# UD3_1_Bootstrap_Gate_Driver.net
KiCad netlist of a schematic drawn in Altium Designer
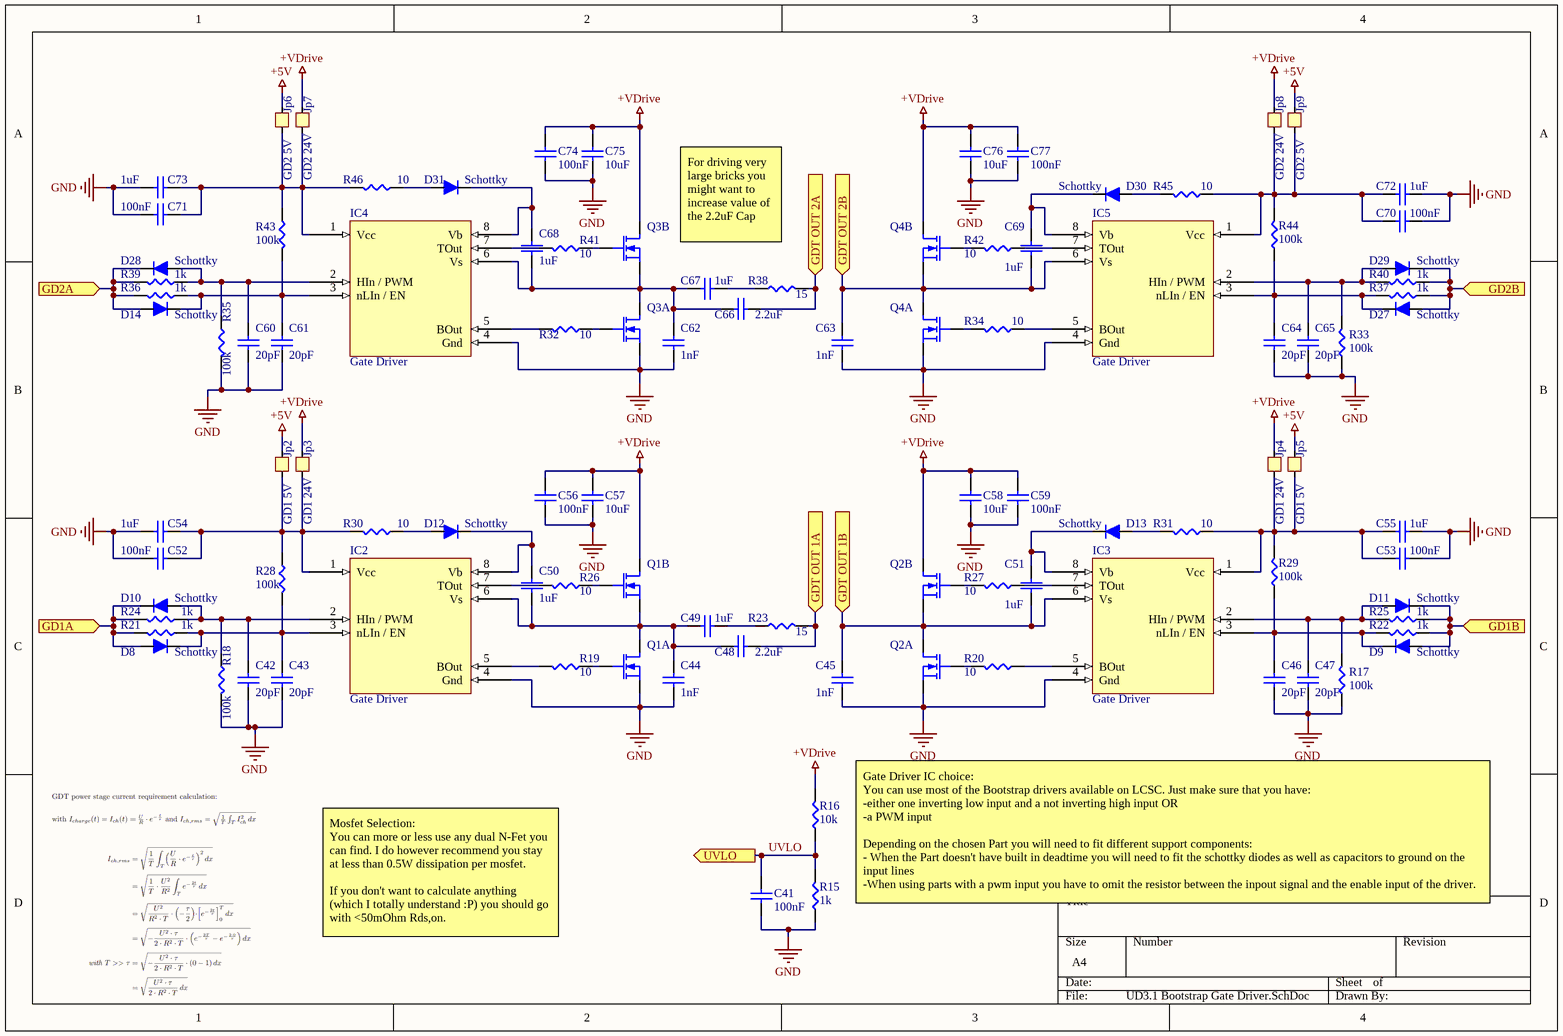
[diagram p0: UD3.1 Bootstrap Gate Driver.SchDoc]

(export (version "E")
  (design (tool "Eeschema 10.0.6"))
  (components
    (comp (ref "C41") (value "100nF") (footprint "0603") (libsource (lib "stdLib") (part "Cap")))
    (comp (ref "C42") (value "20pF") (footprint "0603") (libsource (lib "stdLib") (part "Cap")))
    (comp (ref "C43") (value "20pF") (footprint "0603") (libsource (lib "stdLib") (part "Cap")))
    (comp (ref "C44") (value "1nF") (footprint "0805") (libsource (lib "stdLib") (part "Cap")))
    (comp (ref "C45") (value "1nF") (footprint "0805") (libsource (lib "stdLib") (part "Cap")))
    (comp (ref "C46") (value "20pF") (footprint "0603") (libsource (lib "stdLib") (part "Cap")))
    (comp (ref "C47") (value "20pF") (footprint "0603") (libsource (lib "stdLib") (part "Cap")))
    (comp (ref "C48") (value "2.2uF") (footprint "1206") (libsource (lib "stdLib") (part "Cap")))
    (comp (ref "C49") (value "1uF") (footprint "1206") (libsource (lib "stdLib") (part "Cap")))
    (comp (ref "C50") (value "1uF") (footprint "0805") (libsource (lib "stdLib") (part "Cap")))
    (comp (ref "C51") (value "1uF") (footprint "0805") (libsource (lib "stdLib") (part "Cap")))
    (comp (ref "C52") (value "100nF") (footprint "0603") (libsource (lib "stdLib") (part "Cap")))
    (comp (ref "C53") (value "100nF") (footprint "0603") (libsource (lib "stdLib") (part "Cap")))
    (comp (ref "C54") (value "1uF") (footprint "0805") (libsource (lib "stdLib") (part "Cap")))
    (comp (ref "C55") (value "1uF") (footprint "0805") (libsource (lib "stdLib") (part "Cap")))
    (comp (ref "C56") (value "100nF") (footprint "0603") (libsource (lib "stdLib") (part "Cap")))
    (comp (ref "C57") (value "10uF") (footprint "0805") (libsource (lib "stdLib") (part "Cap")))
    (comp (ref "C58") (value "10uF") (footprint "0805") (libsource (lib "stdLib") (part "Cap")))
    (comp (ref "C59") (value "100nF") (footprint "0603") (libsource (lib "stdLib") (part "Cap")))
    (comp (ref "C60") (value "20pF") (footprint "0603") (libsource (lib "stdLib") (part "Cap")))
    (comp (ref "C61") (value "20pF") (footprint "0603") (libsource (lib "stdLib") (part "Cap")))
    (comp (ref "C62") (value "1nF") (footprint "0805") (libsource (lib "stdLib") (part "Cap")))
    (comp (ref "C63") (value "1nF") (footprint "0805") (libsource (lib "stdLib") (part "Cap")))
    (comp (ref "C64") (value "20pF") (footprint "0603") (libsource (lib "stdLib") (part "Cap")))
    (comp (ref "C65") (value "20pF") (footprint "0603") (libsource (lib "stdLib") (part "Cap")))
    (comp (ref "C66") (value "2.2uF") (footprint "1206") (libsource (lib "stdLib") (part "Cap")))
    (comp (ref "C67") (value "1uF") (footprint "1206") (libsource (lib "stdLib") (part "Cap")))
    (comp (ref "C68") (value "1uF") (footprint "0805") (libsource (lib "stdLib") (part "Cap")))
    (comp (ref "C69") (value "1uF") (footprint "0805") (libsource (lib "stdLib") (part "Cap")))
    (comp (ref "C70") (value "100nF") (footprint "0805") (libsource (lib "stdLib") (part "Cap")))
    (comp (ref "C71") (value "100nF") (footprint "0805") (libsource (lib "stdLib") (part "Cap")))
    (comp (ref "C72") (value "1uF") (footprint "0805") (libsource (lib "stdLib") (part "Cap")))
    (comp (ref "C73") (value "1uF") (footprint "0805") (libsource (lib "stdLib") (part "Cap")))
    (comp (ref "C74") (value "100nF") (footprint "0805") (libsource (lib "stdLib") (part "Cap")))
    (comp (ref "C75") (value "10uF") (footprint "0805") (libsource (lib "stdLib") (part "Cap")))
    (comp (ref "C76") (value "10uF") (footprint "0805") (libsource (lib "stdLib") (part "Cap")))
    (comp (ref "C77") (value "100nF") (footprint "0805") (libsource (lib "stdLib") (part "Cap")))
    (comp (ref "D8")
      (value "Schottky")
      (footprint "SOD523")
      (description "Cmon its a diode what more do I need to say?")
      (libsource (lib "stdLib") (part "Diode"))
    )
    (comp (ref "D9")
      (value "Schottky")
      (footprint "SOD523")
      (description "Cmon its a diode what more do I need to say?")
      (libsource (lib "stdLib") (part "Diode"))
    )
    (comp (ref "D10")
      (value "Schottky")
      (footprint "SOD523")
      (description "Cmon its a diode what more do I need to say?")
      (libsource (lib "stdLib") (part "Diode"))
    )
    (comp (ref "D11")
      (value "Schottky")
      (footprint "SOD523")
      (description "Cmon its a diode what more do I need to say?")
      (libsource (lib "stdLib") (part "Diode"))
    )
    (comp (ref "D12")
      (value "Schottky")
      (footprint "SOD523")
      (description "Cmon its a diode what more do I need to say?")
      (libsource (lib "stdLib") (part "Diode"))
    )
    (comp (ref "D13")
      (value "Schottky")
      (footprint "SOD523")
      (description "Cmon its a diode what more do I need to say?")
      (libsource (lib "stdLib") (part "Diode"))
    )
    (comp (ref "D14")
      (value "Schottky")
      (footprint "SOD523")
      (description "Cmon its a diode what more do I need to say?")
      (libsource (lib "stdLib") (part "Diode"))
    )
    (comp (ref "D27")
      (value "Schottky")
      (footprint "SOD523")
      (description "Cmon its a diode what more do I need to say?")
      (libsource (lib "stdLib") (part "Diode"))
    )
    (comp (ref "D28")
      (value "Schottky")
      (footprint "SOD523")
      (description "Cmon its a diode what more do I need to say?")
      (libsource (lib "stdLib") (part "Diode"))
    )
    (comp (ref "D29")
      (value "Schottky")
      (footprint "SOD523")
      (description "Cmon its a diode what more do I need to say?")
      (libsource (lib "stdLib") (part "Diode"))
    )
    (comp (ref "D30")
      (value "Schottky")
      (footprint "SOD523")
      (description "Cmon its a diode what more do I need to say?")
      (libsource (lib "stdLib") (part "Diode"))
    )
    (comp (ref "D31")
      (value "Schottky")
      (footprint "SOD523")
      (description "Cmon its a diode what more do I need to say?")
      (libsource (lib "stdLib") (part "Diode"))
    )
    (comp (ref "IC2")
      (value "Gate Driver")
      (footprint "SOIC8")
      (description "Bootstrappable half bridge driver IC")
      (libsource (lib "stdLib") (part "Gatedriver Bootstrap"))
    )
    (comp (ref "IC3")
      (value "Gate Driver")
      (footprint "SOIC8")
      (description "Bootstrappable half bridge driver IC")
      (libsource (lib "") (part "Gatedriver Bootstrap_1"))
    )
    (comp (ref "IC4")
      (value "Gate Driver")
      (footprint "SOIC8")
      (description "Bootstrappable half bridge driver IC")
      (libsource (lib "stdLib") (part "Gatedriver Bootstrap"))
    )
    (comp (ref "IC5")
      (value "Gate Driver")
      (footprint "SOIC8")
      (description "Bootstrappable half bridge driver IC")
      (libsource (lib "") (part "Gatedriver Bootstrap_1"))
    )
    (comp (ref "Jp2") (value "GD1 5V") (footprint "PCB Jumper NO") (libsource (lib "") (part "Jumper_1")))
    (comp (ref "Jp3") (value "GD1 24V") (footprint "PCB Jumper NO") (libsource (lib "") (part "Jumper_1")))
    (comp (ref "Jp4")
      (value "GD1 24V")
      (footprint "PCB Jumper NO")
      (libsource (lib "stdLib") (part "Jumper"))
    )
    (comp (ref "Jp5") (value "GD1 5V") (footprint "PCB Jumper NO") (libsource (lib "stdLib") (part "Jumper")))
    (comp (ref "Jp6") (value "GD2 5V") (footprint "PCB Jumper NO") (libsource (lib "") (part "Jumper_1")))
    (comp (ref "Jp7") (value "GD2 24V") (footprint "PCB Jumper NO") (libsource (lib "") (part "Jumper_1")))
    (comp (ref "Jp8")
      (value "GD2 24V")
      (footprint "PCB Jumper NO")
      (libsource (lib "stdLib") (part "Jumper"))
    )
    (comp (ref "Jp9") (value "GD2 5V") (footprint "PCB Jumper NO") (libsource (lib "stdLib") (part "Jumper")))
    (comp (ref "Q1")
      (value "Dual NFet")
      (footprint "SO-8FL - Dual")
      (description "Dual Mosfet, two N channel")
      (libsource (lib "stdLib") (part "Mosfet 2N"))
    )
    (comp (ref "Q2")
      (value "Dual NFet")
      (footprint "SO-8FL - Dual")
      (description "Dual Mosfet, two N channel")
      (libsource (lib "stdLib") (part "Mosfet 2N"))
    )
    (comp (ref "Q3")
      (value "Dual NFet")
      (footprint "SO-8FL - Dual")
      (description "Dual Mosfet, two N channel")
      (libsource (lib "stdLib") (part "Mosfet 2N"))
    )
    (comp (ref "Q4")
      (value "Dual NFet")
      (footprint "SO-8FL - Dual")
      (description "Dual Mosfet, two N channel")
      (libsource (lib "stdLib") (part "Mosfet 2N"))
    )
    (comp (ref "R15") (value "1k") (footprint "0603") (libsource (lib "stdLib") (part "Resistor")))
    (comp (ref "R16") (value "10k") (footprint "0603") (libsource (lib "stdLib") (part "Resistor")))
    (comp (ref "R17") (value "100k") (footprint "0603") (libsource (lib "stdLib") (part "Resistor")))
    (comp (ref "R18") (value "100k") (footprint "0603") (libsource (lib "stdLib") (part "Resistor")))
    (comp (ref "R19") (value "10") (footprint "0805") (libsource (lib "stdLib") (part "Resistor")))
    (comp (ref "R20") (value "10") (footprint "0805") (libsource (lib "stdLib") (part "Resistor")))
    (comp (ref "R21") (value "1k") (footprint "0603") (libsource (lib "stdLib") (part "Resistor")))
    (comp (ref "R22") (value "1k") (footprint "0603") (libsource (lib "stdLib") (part "Resistor")))
    (comp (ref "R23") (value "15") (footprint "1206") (libsource (lib "stdLib") (part "Resistor")))
    (comp (ref "R24") (value "1k") (footprint "0603") (libsource (lib "stdLib") (part "Resistor")))
    (comp (ref "R25") (value "1k") (footprint "0603") (libsource (lib "stdLib") (part "Resistor")))
    (comp (ref "R26") (value "10") (footprint "0805") (libsource (lib "stdLib") (part "Resistor")))
    (comp (ref "R27") (value "10") (footprint "0805") (libsource (lib "stdLib") (part "Resistor")))
    (comp (ref "R28") (value "100k") (footprint "0603") (libsource (lib "stdLib") (part "Resistor")))
    (comp (ref "R29") (value "100k") (footprint "0603") (libsource (lib "stdLib") (part "Resistor")))
    (comp (ref "R30") (value "10") (footprint "0603") (libsource (lib "stdLib") (part "Resistor")))
    (comp (ref "R31") (value "10") (footprint "0603") (libsource (lib "stdLib") (part "Resistor")))
    (comp (ref "R32") (value "10") (footprint "0805") (libsource (lib "stdLib") (part "Resistor")))
    (comp (ref "R33") (value "100k") (footprint "0603") (libsource (lib "stdLib") (part "Resistor")))
    (comp (ref "R34") (value "10") (footprint "0805") (libsource (lib "stdLib") (part "Resistor")))
    (comp (ref "R35") (value "100k") (footprint "0603") (libsource (lib "stdLib") (part "Resistor")))
    (comp (ref "R36") (value "1k") (footprint "0603") (libsource (lib "stdLib") (part "Resistor")))
    (comp (ref "R37") (value "1k") (footprint "0603") (libsource (lib "stdLib") (part "Resistor")))
    (comp (ref "R38") (value "15") (footprint "1206") (libsource (lib "stdLib") (part "Resistor")))
    (comp (ref "R39") (value "1k") (footprint "0603") (libsource (lib "stdLib") (part "Resistor")))
    (comp (ref "R40") (value "1k") (footprint "0603") (libsource (lib "stdLib") (part "Resistor")))
    (comp (ref "R41") (value "10") (footprint "0805") (libsource (lib "stdLib") (part "Resistor")))
    (comp (ref "R42") (value "10") (footprint "0805") (libsource (lib "stdLib") (part "Resistor")))
    (comp (ref "R43") (value "100k") (footprint "0603") (libsource (lib "stdLib") (part "Resistor")))
    (comp (ref "R44") (value "100k") (footprint "0603") (libsource (lib "stdLib") (part "Resistor")))
    (comp (ref "R45") (value "10") (footprint "0603") (libsource (lib "stdLib") (part "Resistor")))
    (comp (ref "R46") (value "10") (footprint "0603") (libsource (lib "stdLib") (part "Resistor")))
  )
  (nets
    (net (code "1") (name "+5V") (class "Default")
      (node (ref "Jp2") (pin "2") (pinfunction "2_2") (pintype "passive"))
      (node (ref "Jp5") (pin "2") (pinfunction "2_2") (pintype "passive"))
      (node (ref "Jp6") (pin "2") (pinfunction "2_2") (pintype "passive"))
      (node (ref "Jp9") (pin "2") (pinfunction "2_2") (pintype "passive"))
    )
    (net (code "2") (name "+VDrive") (class "Default")
      (node (ref "C56") (pin "2") (pinfunction "2_2") (pintype "passive"))
      (node (ref "C57") (pin "2") (pinfunction "2_2") (pintype "passive"))
      (node (ref "C58") (pin "2") (pinfunction "2_2") (pintype "passive"))
      (node (ref "C59") (pin "2") (pinfunction "2_2") (pintype "passive"))
      (node (ref "C74") (pin "2") (pinfunction "2_2") (pintype "passive"))
      (node (ref "C75") (pin "2") (pinfunction "2_2") (pintype "passive"))
      (node (ref "C76") (pin "2") (pinfunction "2_2") (pintype "passive"))
      (node (ref "C77") (pin "2") (pinfunction "2_2") (pintype "passive"))
      (node (ref "Jp3") (pin "2") (pinfunction "2_2") (pintype "passive"))
      (node (ref "Jp4") (pin "2") (pinfunction "2_2") (pintype "passive"))
      (node (ref "Jp7") (pin "2") (pinfunction "2_2") (pintype "passive"))
      (node (ref "Jp8") (pin "2") (pinfunction "2_2") (pintype "passive"))
      (node (ref "Q1") (pin "D1") (pinfunction "D1_D1") (pintype "passive"))
      (node (ref "Q2") (pin "D1") (pinfunction "D1_D1") (pintype "passive"))
      (node (ref "Q3") (pin "D1") (pinfunction "D1_D1") (pintype "passive"))
      (node (ref "Q4") (pin "D1") (pinfunction "D1_D1") (pintype "passive"))
      (node (ref "R16") (pin "1") (pinfunction "1_1") (pintype "passive"))
    )
    (net (code "3") (name "/GD1A") (class "Default")
      (node (ref "D10") (pin "2") (pintype "passive"))
      (node (ref "D8") (pin "1") (pintype "passive"))
      (node (ref "R21") (pin "1") (pinfunction "1_1") (pintype "passive"))
      (node (ref "R24") (pin "1") (pinfunction "1_1") (pintype "passive"))
    )
    (net (code "4") (name "/GD1B") (class "Default")
      (node (ref "D11") (pin "2") (pintype "passive"))
      (node (ref "D9") (pin "1") (pintype "passive"))
      (node (ref "R22") (pin "1") (pinfunction "1_1") (pintype "passive"))
      (node (ref "R25") (pin "1") (pinfunction "1_1") (pintype "passive"))
    )
    (net (code "5") (name "/GD2A") (class "Default")
      (node (ref "D14") (pin "1") (pintype "passive"))
      (node (ref "D28") (pin "2") (pintype "passive"))
      (node (ref "R36") (pin "1") (pinfunction "1_1") (pintype "passive"))
      (node (ref "R39") (pin "1") (pinfunction "1_1") (pintype "passive"))
    )
    (net (code "6") (name "/GD2B") (class "Default")
      (node (ref "D27") (pin "1") (pintype "passive"))
      (node (ref "D29") (pin "2") (pintype "passive"))
      (node (ref "R37") (pin "1") (pinfunction "1_1") (pintype "passive"))
      (node (ref "R40") (pin "1") (pinfunction "1_1") (pintype "passive"))
    )
    (net (code "7") (name "/GDT OUT 1A") (class "Default")
      (node (ref "C48") (pin "2") (pinfunction "2_2") (pintype "passive"))
      (node (ref "R23") (pin "2") (pinfunction "2_2") (pintype "passive"))
    )
    (net (code "8") (name "/GDT OUT 1B") (class "Default")
      (node (ref "C45") (pin "2") (pinfunction "2_2") (pintype "passive"))
      (node (ref "C51") (pin "1") (pinfunction "1_1") (pintype "passive"))
      (node (ref "IC3") (pin "6") (pinfunction "Vs_6") (pintype "input"))
      (node (ref "Q2") (pin "D2") (pinfunction "D2_D2") (pintype "passive"))
      (node (ref "Q2") (pin "S1") (pinfunction "S1_S1") (pintype "passive"))
    )
    (net (code "9") (name "/GDT OUT 2A") (class "Default")
      (node (ref "C66") (pin "2") (pinfunction "2_2") (pintype "passive"))
      (node (ref "R38") (pin "2") (pinfunction "2_2") (pintype "passive"))
    )
    (net (code "10") (name "/GDT OUT 2B") (class "Default")
      (node (ref "C63") (pin "2") (pinfunction "2_2") (pintype "passive"))
      (node (ref "C69") (pin "1") (pinfunction "1_1") (pintype "passive"))
      (node (ref "IC5") (pin "6") (pinfunction "Vs_6") (pintype "input"))
      (node (ref "Q4") (pin "D2") (pinfunction "D2_D2") (pintype "passive"))
      (node (ref "Q4") (pin "S1") (pinfunction "S1_S1") (pintype "passive"))
    )
    (net (code "11") (name "/UVLO") (class "Default")
      (node (ref "C41") (pin "2") (pinfunction "2_2") (pintype "passive"))
      (node (ref "R15") (pin "1") (pinfunction "1_1") (pintype "passive"))
      (node (ref "R16") (pin "2") (pinfunction "2_2") (pintype "passive"))
    )
    (net (code "12") (name "GND") (class "Default")
      (node (ref "C41") (pin "1") (pinfunction "1_1") (pintype "passive"))
      (node (ref "C42") (pin "2") (pinfunction "2_2") (pintype "passive"))
      (node (ref "C43") (pin "2") (pinfunction "2_2") (pintype "passive"))
      (node (ref "C44") (pin "1") (pinfunction "1_1") (pintype "passive"))
      (node (ref "C45") (pin "1") (pinfunction "1_1") (pintype "passive"))
      (node (ref "C46") (pin "2") (pinfunction "2_2") (pintype "passive"))
      (node (ref "C47") (pin "2") (pinfunction "2_2") (pintype "passive"))
      (node (ref "C52") (pin "2") (pinfunction "2_2") (pintype "passive"))
      (node (ref "C53") (pin "2") (pinfunction "2_2") (pintype "passive"))
      (node (ref "C54") (pin "2") (pinfunction "2_2") (pintype "passive"))
      (node (ref "C55") (pin "2") (pinfunction "2_2") (pintype "passive"))
      (node (ref "C56") (pin "1") (pinfunction "1_1") (pintype "passive"))
      (node (ref "C57") (pin "1") (pinfunction "1_1") (pintype "passive"))
      (node (ref "C58") (pin "1") (pinfunction "1_1") (pintype "passive"))
      (node (ref "C59") (pin "1") (pinfunction "1_1") (pintype "passive"))
      (node (ref "C60") (pin "2") (pinfunction "2_2") (pintype "passive"))
      (node (ref "C61") (pin "2") (pinfunction "2_2") (pintype "passive"))
      (node (ref "C62") (pin "1") (pinfunction "1_1") (pintype "passive"))
      (node (ref "C63") (pin "1") (pinfunction "1_1") (pintype "passive"))
      (node (ref "C64") (pin "2") (pinfunction "2_2") (pintype "passive"))
      (node (ref "C65") (pin "2") (pinfunction "2_2") (pintype "passive"))
      (node (ref "C70") (pin "2") (pinfunction "2_2") (pintype "passive"))
      (node (ref "C71") (pin "2") (pinfunction "2_2") (pintype "passive"))
      (node (ref "C72") (pin "2") (pinfunction "2_2") (pintype "passive"))
      (node (ref "C73") (pin "2") (pinfunction "2_2") (pintype "passive"))
      (node (ref "C74") (pin "1") (pinfunction "1_1") (pintype "passive"))
      (node (ref "C75") (pin "1") (pinfunction "1_1") (pintype "passive"))
      (node (ref "C76") (pin "1") (pinfunction "1_1") (pintype "passive"))
      (node (ref "C77") (pin "1") (pinfunction "1_1") (pintype "passive"))
      (node (ref "IC2") (pin "4") (pinfunction "Gnd_4") (pintype "input"))
      (node (ref "IC3") (pin "4") (pinfunction "Gnd_4") (pintype "input"))
      (node (ref "IC4") (pin "4") (pinfunction "Gnd_4") (pintype "input"))
      (node (ref "IC5") (pin "4") (pinfunction "Gnd_4") (pintype "input"))
      (node (ref "Q1") (pin "S2") (pinfunction "S2_S2") (pintype "passive"))
      (node (ref "Q2") (pin "S2") (pinfunction "S2_S2") (pintype "passive"))
      (node (ref "Q3") (pin "S2") (pinfunction "S2_S2") (pintype "passive"))
      (node (ref "Q4") (pin "S2") (pinfunction "S2_S2") (pintype "passive"))
      (node (ref "R15") (pin "2") (pinfunction "2_2") (pintype "passive"))
      (node (ref "R17") (pin "1") (pinfunction "1_1") (pintype "passive"))
      (node (ref "R18") (pin "1") (pinfunction "1_1") (pintype "passive"))
      (node (ref "R33") (pin "1") (pinfunction "1_1") (pintype "passive"))
      (node (ref "R35") (pin "1") (pinfunction "1_1") (pintype "passive"))
    )
    (net (code "13") (name "Net-(C49-Pad2)") (class "Default")
      (node (ref "C49") (pin "2") (pinfunction "2_2") (pintype "passive"))
      (node (ref "R23") (pin "1") (pinfunction "1_1") (pintype "passive"))
    )
    (net (code "14") (name "Net-(C67-Pad2)") (class "Default")
      (node (ref "C67") (pin "2") (pinfunction "2_2") (pintype "passive"))
      (node (ref "R38") (pin "1") (pinfunction "1_1") (pintype "passive"))
    )
    (net (code "15") (name "Net-(D12-Pad1)") (class "Default")
      (node (ref "D12") (pin "1") (pintype "passive"))
      (node (ref "R30") (pin "2") (pinfunction "2_2") (pintype "passive"))
    )
    (net (code "16") (name "Net-(D13-Pad1)") (class "Default")
      (node (ref "D13") (pin "1") (pintype "passive"))
      (node (ref "R31") (pin "2") (pinfunction "2_2") (pintype "passive"))
    )
    (net (code "17") (name "Net-(D30-Pad1)") (class "Default")
      (node (ref "D30") (pin "1") (pintype "passive"))
      (node (ref "R45") (pin "2") (pinfunction "2_2") (pintype "passive"))
    )
    (net (code "18") (name "Net-(D31-Pad1)") (class "Default")
      (node (ref "D31") (pin "1") (pintype "passive"))
      (node (ref "R46") (pin "2") (pinfunction "2_2") (pintype "passive"))
    )
    (net (code "19") (name "Net-(IC2-BOut)") (class "Default")
      (node (ref "IC2") (pin "5") (pinfunction "BOut_5") (pintype "input"))
      (node (ref "R19") (pin "1") (pinfunction "1_1") (pintype "passive"))
    )
    (net (code "20") (name "Net-(IC2-HIn_{slash}_PWM)") (class "Default")
      (node (ref "C42") (pin "1") (pinfunction "1_1") (pintype "passive"))
      (node (ref "D10") (pin "1") (pintype "passive"))
      (node (ref "IC2") (pin "2") (pinfunction "HIn_/_PWM_2") (pintype "input"))
      (node (ref "R18") (pin "2") (pinfunction "2_2") (pintype "passive"))
      (node (ref "R24") (pin "2") (pinfunction "2_2") (pintype "passive"))
    )
    (net (code "21") (name "Net-(IC2-TOut)") (class "Default")
      (node (ref "IC2") (pin "7") (pinfunction "TOut_7") (pintype "input"))
      (node (ref "R26") (pin "1") (pinfunction "1_1") (pintype "passive"))
    )
    (net (code "22") (name "Net-(IC2-Vb)") (class "Default")
      (node (ref "C50") (pin "2") (pinfunction "2_2") (pintype "passive"))
      (node (ref "D12") (pin "2") (pintype "passive"))
      (node (ref "IC2") (pin "8") (pinfunction "Vb_8") (pintype "input"))
    )
    (net (code "23") (name "Net-(IC2-Vcc)") (class "Default")
      (node (ref "C52") (pin "1") (pinfunction "1_1") (pintype "passive"))
      (node (ref "C54") (pin "1") (pinfunction "1_1") (pintype "passive"))
      (node (ref "IC2") (pin "1") (pinfunction "Vcc_1") (pintype "input"))
      (node (ref "Jp2") (pin "1") (pinfunction "1_1") (pintype "passive"))
      (node (ref "Jp3") (pin "1") (pinfunction "1_1") (pintype "passive"))
      (node (ref "R28") (pin "2") (pinfunction "2_2") (pintype "passive"))
      (node (ref "R30") (pin "1") (pinfunction "1_1") (pintype "passive"))
    )
    (net (code "24") (name "Net-(IC2-Vs)") (class "Default")
      (node (ref "C44") (pin "2") (pinfunction "2_2") (pintype "passive"))
      (node (ref "C48") (pin "1") (pinfunction "1_1") (pintype "passive"))
      (node (ref "C49") (pin "1") (pinfunction "1_1") (pintype "passive"))
      (node (ref "C50") (pin "1") (pinfunction "1_1") (pintype "passive"))
      (node (ref "IC2") (pin "6") (pinfunction "Vs_6") (pintype "input"))
      (node (ref "Q1") (pin "D2") (pinfunction "D2_D2") (pintype "passive"))
      (node (ref "Q1") (pin "S1") (pinfunction "S1_S1") (pintype "passive"))
    )
    (net (code "25") (name "Net-(IC2-nLIn_{slash}_EN)") (class "Default")
      (node (ref "C43") (pin "1") (pinfunction "1_1") (pintype "passive"))
      (node (ref "D8") (pin "2") (pintype "passive"))
      (node (ref "IC2") (pin "3") (pinfunction "nLIn_/_EN_3") (pintype "input"))
      (node (ref "R21") (pin "2") (pinfunction "2_2") (pintype "passive"))
      (node (ref "R28") (pin "1") (pinfunction "1_1") (pintype "passive"))
    )
    (net (code "26") (name "Net-(IC3-BOut)") (class "Default")
      (node (ref "IC3") (pin "5") (pinfunction "BOut_5") (pintype "input"))
      (node (ref "R20") (pin "1") (pinfunction "1_1") (pintype "passive"))
    )
    (net (code "27") (name "Net-(IC3-HIn_{slash}_PWM)") (class "Default")
      (node (ref "C47") (pin "1") (pinfunction "1_1") (pintype "passive"))
      (node (ref "D11") (pin "1") (pintype "passive"))
      (node (ref "IC3") (pin "2") (pinfunction "HIn_/_PWM_2") (pintype "input"))
      (node (ref "R17") (pin "2") (pinfunction "2_2") (pintype "passive"))
      (node (ref "R25") (pin "2") (pinfunction "2_2") (pintype "passive"))
    )
    (net (code "28") (name "Net-(IC3-TOut)") (class "Default")
      (node (ref "IC3") (pin "7") (pinfunction "TOut_7") (pintype "input"))
      (node (ref "R27") (pin "1") (pinfunction "1_1") (pintype "passive"))
    )
    (net (code "29") (name "Net-(IC3-Vb)") (class "Default")
      (node (ref "C51") (pin "2") (pinfunction "2_2") (pintype "passive"))
      (node (ref "D13") (pin "2") (pintype "passive"))
      (node (ref "IC3") (pin "8") (pinfunction "Vb_8") (pintype "input"))
    )
    (net (code "30") (name "Net-(IC3-Vcc)") (class "Default")
      (node (ref "C53") (pin "1") (pinfunction "1_1") (pintype "passive"))
      (node (ref "C55") (pin "1") (pinfunction "1_1") (pintype "passive"))
      (node (ref "IC3") (pin "1") (pinfunction "Vcc_1") (pintype "input"))
      (node (ref "Jp4") (pin "1") (pinfunction "1_1") (pintype "passive"))
      (node (ref "Jp5") (pin "1") (pinfunction "1_1") (pintype "passive"))
      (node (ref "R29") (pin "2") (pinfunction "2_2") (pintype "passive"))
      (node (ref "R31") (pin "1") (pinfunction "1_1") (pintype "passive"))
    )
    (net (code "31") (name "Net-(IC3-nLIn_{slash}_EN)") (class "Default")
      (node (ref "C46") (pin "1") (pinfunction "1_1") (pintype "passive"))
      (node (ref "D9") (pin "2") (pintype "passive"))
      (node (ref "IC3") (pin "3") (pinfunction "nLIn_/_EN_3") (pintype "input"))
      (node (ref "R22") (pin "2") (pinfunction "2_2") (pintype "passive"))
      (node (ref "R29") (pin "1") (pinfunction "1_1") (pintype "passive"))
    )
    (net (code "32") (name "Net-(IC4-BOut)") (class "Default")
      (node (ref "IC4") (pin "5") (pinfunction "BOut_5") (pintype "input"))
      (node (ref "R32") (pin "1") (pinfunction "1_1") (pintype "passive"))
    )
    (net (code "33") (name "Net-(IC4-HIn_{slash}_PWM)") (class "Default")
      (node (ref "C60") (pin "1") (pinfunction "1_1") (pintype "passive"))
      (node (ref "D28") (pin "1") (pintype "passive"))
      (node (ref "IC4") (pin "2") (pinfunction "HIn_/_PWM_2") (pintype "input"))
      (node (ref "R35") (pin "2") (pinfunction "2_2") (pintype "passive"))
      (node (ref "R39") (pin "2") (pinfunction "2_2") (pintype "passive"))
    )
    (net (code "34") (name "Net-(IC4-TOut)") (class "Default")
      (node (ref "IC4") (pin "7") (pinfunction "TOut_7") (pintype "input"))
      (node (ref "R41") (pin "1") (pinfunction "1_1") (pintype "passive"))
    )
    (net (code "35") (name "Net-(IC4-Vb)") (class "Default")
      (node (ref "C68") (pin "2") (pinfunction "2_2") (pintype "passive"))
      (node (ref "D31") (pin "2") (pintype "passive"))
      (node (ref "IC4") (pin "8") (pinfunction "Vb_8") (pintype "input"))
    )
    (net (code "36") (name "Net-(IC4-Vcc)") (class "Default")
      (node (ref "C71") (pin "1") (pinfunction "1_1") (pintype "passive"))
      (node (ref "C73") (pin "1") (pinfunction "1_1") (pintype "passive"))
      (node (ref "IC4") (pin "1") (pinfunction "Vcc_1") (pintype "input"))
      (node (ref "Jp6") (pin "1") (pinfunction "1_1") (pintype "passive"))
      (node (ref "Jp7") (pin "1") (pinfunction "1_1") (pintype "passive"))
      (node (ref "R43") (pin "2") (pinfunction "2_2") (pintype "passive"))
      (node (ref "R46") (pin "1") (pinfunction "1_1") (pintype "passive"))
    )
    (net (code "37") (name "Net-(IC4-Vs)") (class "Default")
      (node (ref "C62") (pin "2") (pinfunction "2_2") (pintype "passive"))
      (node (ref "C66") (pin "1") (pinfunction "1_1") (pintype "passive"))
      (node (ref "C67") (pin "1") (pinfunction "1_1") (pintype "passive"))
      (node (ref "C68") (pin "1") (pinfunction "1_1") (pintype "passive"))
      (node (ref "IC4") (pin "6") (pinfunction "Vs_6") (pintype "input"))
      (node (ref "Q3") (pin "D2") (pinfunction "D2_D2") (pintype "passive"))
      (node (ref "Q3") (pin "S1") (pinfunction "S1_S1") (pintype "passive"))
    )
    (net (code "38") (name "Net-(IC4-nLIn_{slash}_EN)") (class "Default")
      (node (ref "C61") (pin "1") (pinfunction "1_1") (pintype "passive"))
      (node (ref "D14") (pin "2") (pintype "passive"))
      (node (ref "IC4") (pin "3") (pinfunction "nLIn_/_EN_3") (pintype "input"))
      (node (ref "R36") (pin "2") (pinfunction "2_2") (pintype "passive"))
      (node (ref "R43") (pin "1") (pinfunction "1_1") (pintype "passive"))
    )
    (net (code "39") (name "Net-(IC5-BOut)") (class "Default")
      (node (ref "IC5") (pin "5") (pinfunction "BOut_5") (pintype "input"))
      (node (ref "R34") (pin "1") (pinfunction "1_1") (pintype "passive"))
    )
    (net (code "40") (name "Net-(IC5-HIn_{slash}_PWM)") (class "Default")
      (node (ref "C65") (pin "1") (pinfunction "1_1") (pintype "passive"))
      (node (ref "D29") (pin "1") (pintype "passive"))
      (node (ref "IC5") (pin "2") (pinfunction "HIn_/_PWM_2") (pintype "input"))
      (node (ref "R33") (pin "2") (pinfunction "2_2") (pintype "passive"))
      (node (ref "R40") (pin "2") (pinfunction "2_2") (pintype "passive"))
    )
    (net (code "41") (name "Net-(IC5-TOut)") (class "Default")
      (node (ref "IC5") (pin "7") (pinfunction "TOut_7") (pintype "input"))
      (node (ref "R42") (pin "1") (pinfunction "1_1") (pintype "passive"))
    )
    (net (code "42") (name "Net-(IC5-Vb)") (class "Default")
      (node (ref "C69") (pin "2") (pinfunction "2_2") (pintype "passive"))
      (node (ref "D30") (pin "2") (pintype "passive"))
      (node (ref "IC5") (pin "8") (pinfunction "Vb_8") (pintype "input"))
    )
    (net (code "43") (name "Net-(IC5-Vcc)") (class "Default")
      (node (ref "C70") (pin "1") (pinfunction "1_1") (pintype "passive"))
      (node (ref "C72") (pin "1") (pinfunction "1_1") (pintype "passive"))
      (node (ref "IC5") (pin "1") (pinfunction "Vcc_1") (pintype "input"))
      (node (ref "Jp8") (pin "1") (pinfunction "1_1") (pintype "passive"))
      (node (ref "Jp9") (pin "1") (pinfunction "1_1") (pintype "passive"))
      (node (ref "R44") (pin "2") (pinfunction "2_2") (pintype "passive"))
      (node (ref "R45") (pin "1") (pinfunction "1_1") (pintype "passive"))
    )
    (net (code "44") (name "Net-(IC5-nLIn_{slash}_EN)") (class "Default")
      (node (ref "C64") (pin "1") (pinfunction "1_1") (pintype "passive"))
      (node (ref "D27") (pin "2") (pintype "passive"))
      (node (ref "IC5") (pin "3") (pinfunction "nLIn_/_EN_3") (pintype "input"))
      (node (ref "R37") (pin "2") (pinfunction "2_2") (pintype "passive"))
      (node (ref "R44") (pin "1") (pinfunction "1_1") (pintype "passive"))
    )
    (net (code "45") (name "Net-(Q1-PadG1)") (class "Default")
      (node (ref "Q1") (pin "G1") (pinfunction "G1_G1") (pintype "passive"))
      (node (ref "R26") (pin "2") (pinfunction "2_2") (pintype "passive"))
    )
    (net (code "46") (name "Net-(Q1-PadG2)") (class "Default")
      (node (ref "Q1") (pin "G2") (pinfunction "G2_G2") (pintype "passive"))
      (node (ref "R19") (pin "2") (pinfunction "2_2") (pintype "passive"))
    )
    (net (code "47") (name "Net-(Q2-PadG1)") (class "Default")
      (node (ref "Q2") (pin "G1") (pinfunction "G1_G1") (pintype "passive"))
      (node (ref "R27") (pin "2") (pinfunction "2_2") (pintype "passive"))
    )
    (net (code "48") (name "Net-(Q2-PadG2)") (class "Default")
      (node (ref "Q2") (pin "G2") (pinfunction "G2_G2") (pintype "passive"))
      (node (ref "R20") (pin "2") (pinfunction "2_2") (pintype "passive"))
    )
    (net (code "49") (name "Net-(Q3-PadG1)") (class "Default")
      (node (ref "Q3") (pin "G1") (pinfunction "G1_G1") (pintype "passive"))
      (node (ref "R41") (pin "2") (pinfunction "2_2") (pintype "passive"))
    )
    (net (code "50") (name "Net-(Q3-PadG2)") (class "Default")
      (node (ref "Q3") (pin "G2") (pinfunction "G2_G2") (pintype "passive"))
      (node (ref "R32") (pin "2") (pinfunction "2_2") (pintype "passive"))
    )
    (net (code "51") (name "Net-(Q4-PadG1)") (class "Default")
      (node (ref "Q4") (pin "G1") (pinfunction "G1_G1") (pintype "passive"))
      (node (ref "R42") (pin "2") (pinfunction "2_2") (pintype "passive"))
    )
    (net (code "52") (name "Net-(Q4-PadG2)") (class "Default")
      (node (ref "Q4") (pin "G2") (pinfunction "G2_G2") (pintype "passive"))
      (node (ref "R34") (pin "2") (pinfunction "2_2") (pintype "passive"))
    )
  )
)
